# HighCurrentDriver.net
KiCad netlist of a schematic drawn in Altium Designer
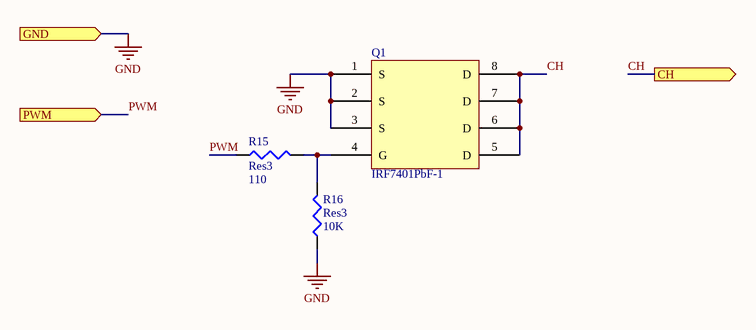
[diagram p0: HighCurrentDriver.SchDoc]

(export (version "E")
  (design (tool "Eeschema 10.0.6"))
  (components
    (comp (ref "Q1")
      (value "IRF7401PbF-1")
      (footprint "SOIC8")
      (description "MOSFET N Channel 20V 8.7A 700mV @ 250uA 22mΩ @ 4.1A,4.5V SOIC-8_150mil RoHS")
      (fields
        (field (name "MANUFACTURER") "Infineon Technologies")
        (field (name "MANUFACTURER PART NUMBER") "IRF7401TRPBF")
      )
      (libsource (lib "IoWLabs") (part "IRF7401"))
    )
    (comp (ref "R15")
      (value "Res3")
      (footprint "J1-0603")
      (description "Resistor")
      (fields
        (field (name "ALTIUM_VALUE") "110")
        (field (name "MANUFACTURER") "ROHM Semicon")
        (field (name "MANUFACTURER PART NUMBER") "MCR03EZPFX1100")
        (field (name "PUBLISHER") "Altium Limited")
      )
      (libsource (lib "Miscellaneous Devices") (part "Res3"))
    )
    (comp (ref "R16")
      (value "Res3")
      (footprint "J1-0603")
      (description "Resistor")
      (fields
        (field (name "ALTIUM_VALUE") "10K")
        (field (name "MANUFACTURER") "PANASONIC")
        (field (name "MANUFACTURER PART NUMBER") "ERJPA3F1002V")
        (field (name "PUBLISHER") "Altium Limited")
      )
      (libsource (lib "Miscellaneous Devices") (part "Res3"))
    )
  )
  (nets
    (net (code "1") (name "/CH") (class "Default")
      (node (ref "Q1") (pin "5") (pinfunction "D_5") (pintype "passive"))
      (node (ref "Q1") (pin "6") (pinfunction "D_6") (pintype "passive"))
      (node (ref "Q1") (pin "7") (pinfunction "D_7") (pintype "passive"))
      (node (ref "Q1") (pin "8") (pinfunction "D_8") (pintype "passive"))
    )
    (net (code "2") (name "/PWM") (class "Default")
      (node (ref "R15") (pin "1") (pinfunction "1_1") (pintype "passive"))
    )
    (net (code "3") (name "GND") (class "Default")
      (node (ref "Q1") (pin "1") (pinfunction "S_1") (pintype "passive"))
      (node (ref "Q1") (pin "2") (pinfunction "S_2") (pintype "passive"))
      (node (ref "Q1") (pin "3") (pinfunction "S_3") (pintype "passive"))
      (node (ref "R16") (pin "1") (pinfunction "1_1") (pintype "passive"))
    )
    (net (code "4") (name "Net-(Q1-G)") (class "Default")
      (node (ref "Q1") (pin "4") (pinfunction "G_4") (pintype "passive"))
      (node (ref "R15") (pin "2") (pinfunction "2_2") (pintype "passive"))
      (node (ref "R16") (pin "2") (pinfunction "2_2") (pintype "passive"))
    )
  )
)
